# IO4-Codeline-Matrix.net
KiCad netlist of a schematic drawn in EAGLE
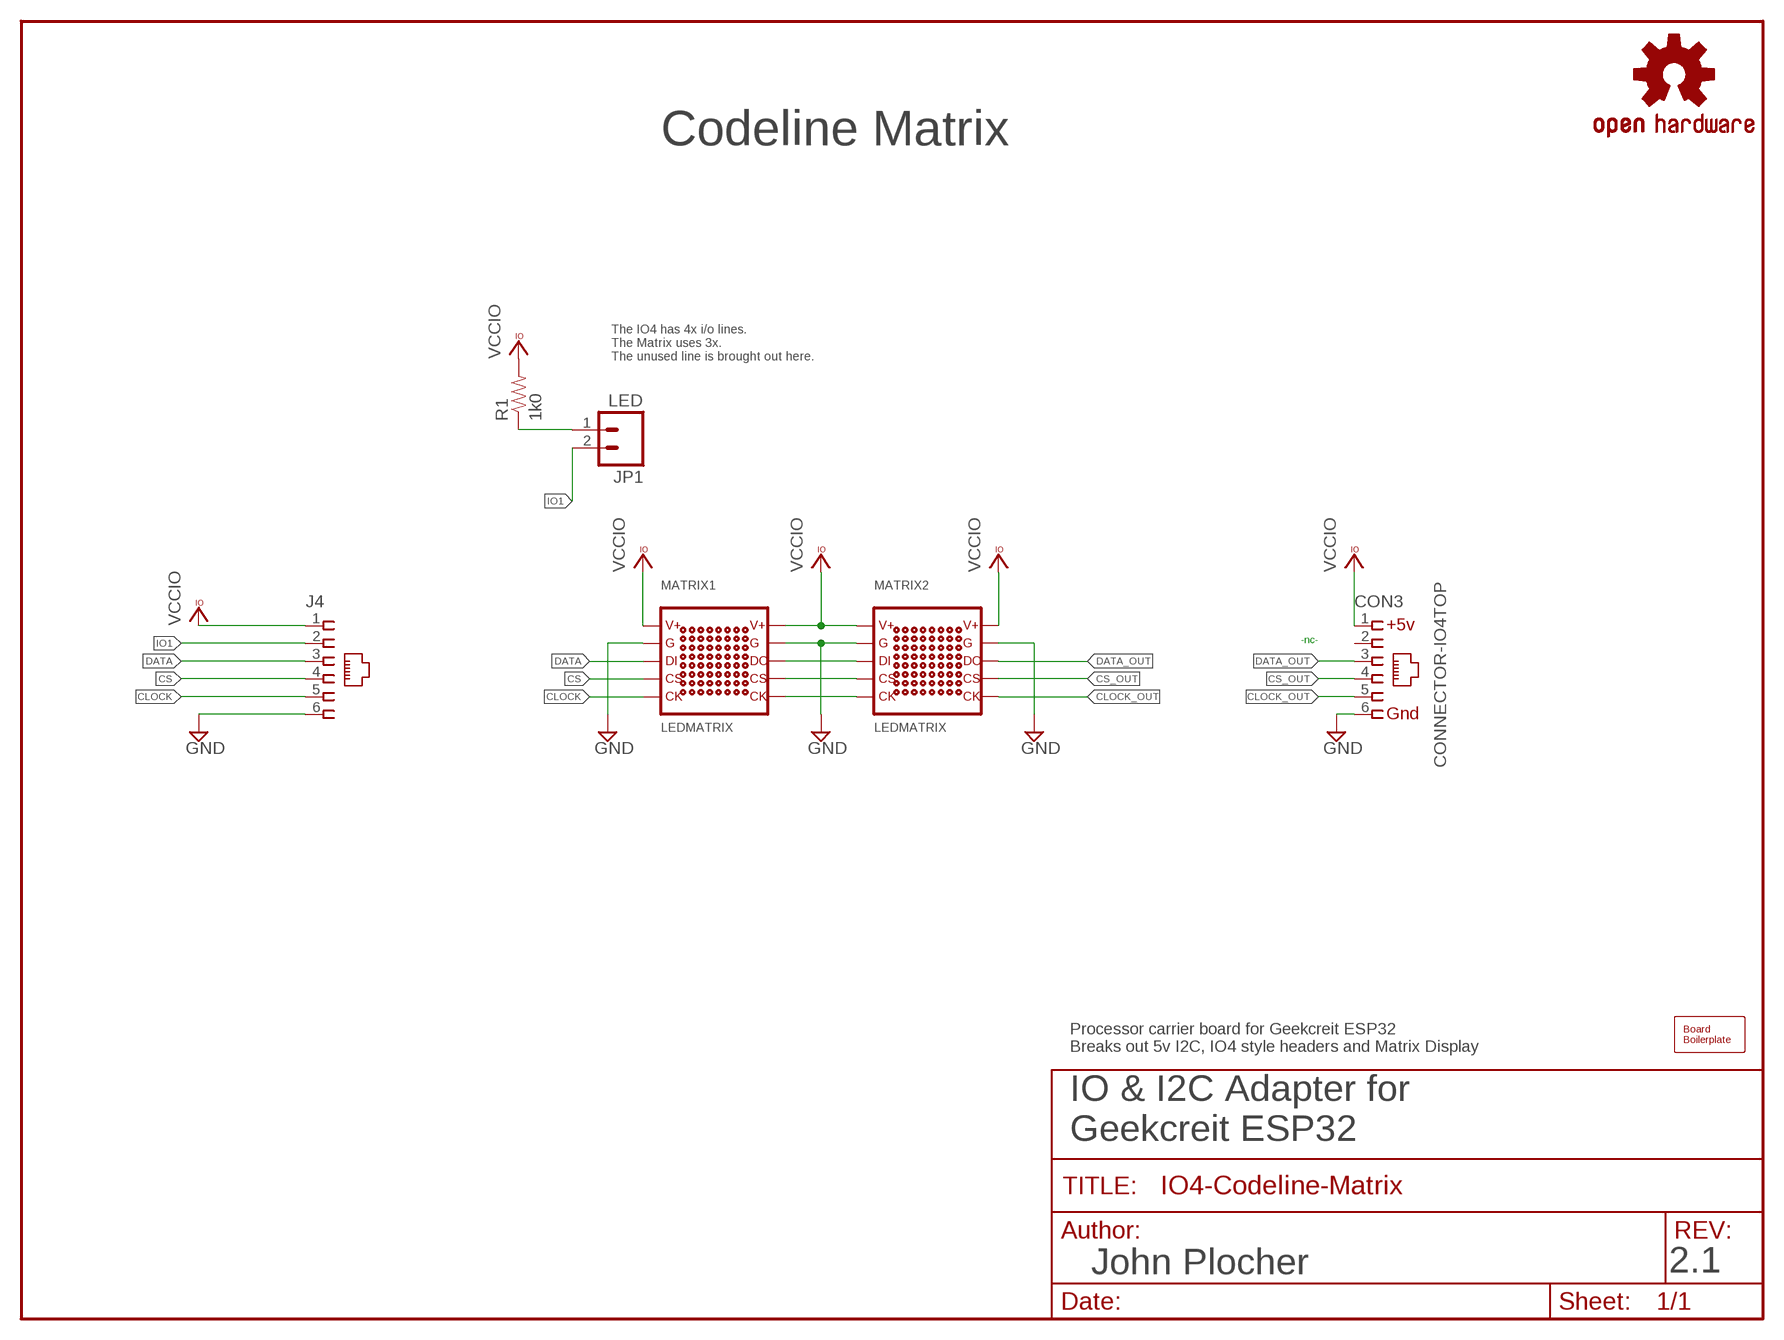
[diagram p0: schematic, sheet 1]

(export (version "E")
  (design (tool "Eeschema 10.0.6"))
  (components
    (comp (ref "BOARD")
      (value "BOARD80X150")
      (footprint "eagle-import:BOARD-DINRAIL-3.17INX8CM")
      (libsource (lib "eagle-import") (part "BOARD80X80"))
    )
    (comp (ref "CON3")
      (value "CONNECTOR-IO4TOP")
      (footprint "eagle-import:RJ25-TOP")
      (libsource (lib "eagle-import") (part "CONNECTOR-IO4TOP"))
    )
    (comp (ref "J4")
      (value "CONNECTOR-RJ25-43860-2-MOLEX")
      (footprint "eagle-import:RJ25-INVERTED")
      (libsource (lib "eagle-import") (part "CONNECTOR-RJ25-43860-2-MOLEX"))
    )
    (comp (ref "JP1")
      (value "LED")
      (footprint "eagle-import:1X02_LOCK")
      (libsource (lib "eagle-import") (part "M02LOCK"))
    )
    (comp (ref "MATRIX1")
      (value "LEDMATRIX")
      (footprint "eagle-import:LEDMATRIX")
      (libsource (lib "eagle-import") (part "LEDMATRIX"))
    )
    (comp (ref "MATRIX2")
      (value "LEDMATRIX")
      (footprint "eagle-import:LEDMATRIX")
      (libsource (lib "eagle-import") (part "LEDMATRIX"))
    )
    (comp (ref "OSHW1")
      (value "OSHW-LOGOL")
      (footprint "eagle-import:OSHW-LOGO-L")
      (libsource (lib "eagle-import") (part "OSHW-LOGOL"))
    )
    (comp (ref "R1")
      (value "1k0")
      (footprint "eagle-import:AXIAL-0.4-RES")
      (libsource (lib "eagle-import") (part "RPTH04"))
    )
  )
  (nets
    (net (code "1") (name "CLOCK") (class "Default")
      (node (ref "J4") (pin "5") (pinfunction "5_5") (pintype "passive"))
      (node (ref "MATRIX1") (pin "CLK@1") (pinfunction "CLK_CLK@1") (pintype "bidirectional"))
    )
    (net (code "2") (name "CLOCK_OUT") (class "Default")
      (node (ref "CON3") (pin "5") (pinfunction "5_5") (pintype "passive"))
      (node (ref "MATRIX2") (pin "CLK@2") (pinfunction "CLK_CLK@2") (pintype "bidirectional"))
    )
    (net (code "3") (name "CS") (class "Default")
      (node (ref "J4") (pin "4") (pinfunction "4_4") (pintype "passive"))
      (node (ref "MATRIX1") (pin "CS@1") (pinfunction "CS_CS@1") (pintype "bidirectional"))
    )
    (net (code "4") (name "CS_OUT") (class "Default")
      (node (ref "CON3") (pin "4") (pinfunction "4_4") (pintype "passive"))
      (node (ref "MATRIX2") (pin "CS@2") (pinfunction "CS_CS@2") (pintype "bidirectional"))
    )
    (net (code "5") (name "DATA") (class "Default")
      (node (ref "J4") (pin "3") (pinfunction "3_3") (pintype "passive"))
      (node (ref "MATRIX1") (pin "DI") (pinfunction "DIN_DI") (pintype "bidirectional"))
    )
    (net (code "6") (name "DATA_OUT") (class "Default")
      (node (ref "CON3") (pin "3") (pinfunction "3_3") (pintype "passive"))
      (node (ref "MATRIX2") (pin "DO") (pinfunction "DOUT_DO") (pintype "bidirectional"))
    )
    (net (code "7") (name "GND") (class "Default")
      (node (ref "CON3") (pin "6") (pinfunction "6_6") (pintype "power_in"))
      (node (ref "J4") (pin "6") (pinfunction "6_6") (pintype "passive"))
      (node (ref "MATRIX1") (pin "G@1") (pinfunction "G_G@1") (pintype "bidirectional"))
      (node (ref "MATRIX1") (pin "G@2") (pinfunction "G_G@2") (pintype "bidirectional"))
      (node (ref "MATRIX2") (pin "G@1") (pinfunction "G_G@1") (pintype "bidirectional"))
      (node (ref "MATRIX2") (pin "G@2") (pinfunction "G_G@2") (pintype "bidirectional"))
    )
    (net (code "8") (name "IO1") (class "Default")
      (node (ref "J4") (pin "2") (pinfunction "2_2") (pintype "passive"))
      (node (ref "JP1") (pin "2") (pinfunction "2_2") (pintype "passive"))
    )
    (net (code "9") (name "Net-(MATRIX1-CLK-PadCLK@2)") (class "Default")
      (node (ref "MATRIX1") (pin "CLK@2") (pinfunction "CLK_CLK@2") (pintype "bidirectional"))
      (node (ref "MATRIX2") (pin "CLK@1") (pinfunction "CLK_CLK@1") (pintype "bidirectional"))
    )
    (net (code "10") (name "Net-(MATRIX1-CS-PadCS@2)") (class "Default")
      (node (ref "MATRIX1") (pin "CS@2") (pinfunction "CS_CS@2") (pintype "bidirectional"))
      (node (ref "MATRIX2") (pin "CS@1") (pinfunction "CS_CS@1") (pintype "bidirectional"))
    )
    (net (code "11") (name "Net-(MATRIX1-DOUT)") (class "Default")
      (node (ref "MATRIX1") (pin "DO") (pinfunction "DOUT_DO") (pintype "bidirectional"))
      (node (ref "MATRIX2") (pin "DI") (pinfunction "DIN_DI") (pintype "bidirectional"))
    )
    (net (code "12") (name "Net-(R1-1)") (class "Default")
      (node (ref "JP1") (pin "1") (pinfunction "1_1") (pintype "passive"))
      (node (ref "R1") (pin "P$1") (pinfunction "1_P$1") (pintype "passive"))
    )
    (net (code "13") (name "VCCIO") (class "Default")
      (node (ref "CON3") (pin "1") (pinfunction "1_1") (pintype "power_in"))
      (node (ref "J4") (pin "1") (pinfunction "1_1") (pintype "passive"))
      (node (ref "MATRIX1") (pin "V+@1") (pinfunction "V+_V+@1") (pintype "bidirectional"))
      (node (ref "MATRIX1") (pin "V+@2") (pinfunction "V+_V+@2") (pintype "bidirectional"))
      (node (ref "MATRIX2") (pin "V+@1") (pinfunction "V+_V+@1") (pintype "bidirectional"))
      (node (ref "MATRIX2") (pin "V+@2") (pinfunction "V+_V+@2") (pintype "bidirectional"))
      (node (ref "R1") (pin "P$2") (pinfunction "2_P$2") (pintype "passive"))
    )
    (net (code "14") (name "unconnected-(CON3-Pad2)") (class "Default")
      (node (ref "CON3") (pin "2") (pinfunction "2_2") (pintype "passive"))
    )
  )
)
